# SD_Holder.net
KiCad netlist of a schematic drawn in Altium Designer
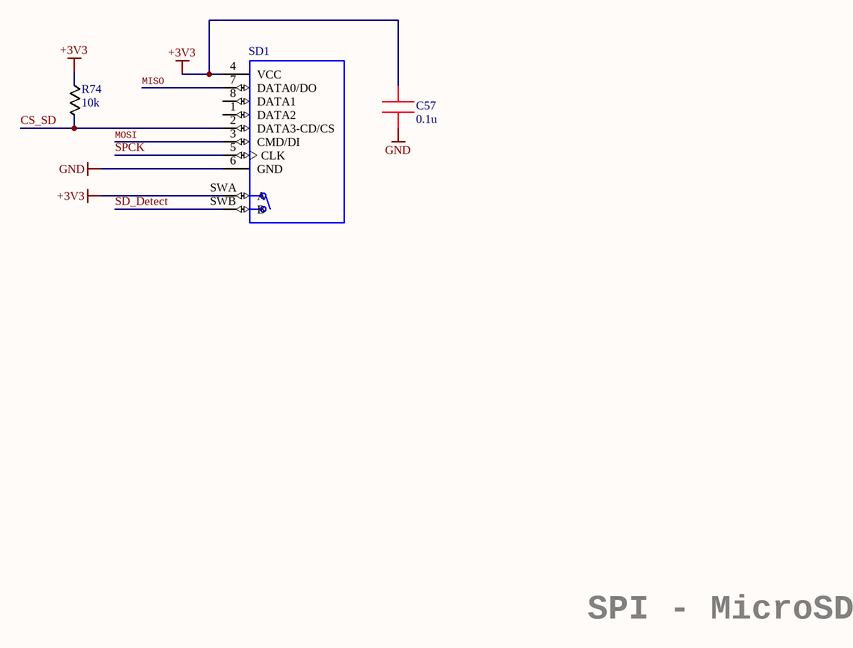
[diagram p0: SD Holder.SchDoc]

(export (version "E")
  (design (tool "Eeschema 10.0.6"))
  (components
    (comp (ref "C57")
      (value "0.1u")
      (footprint "0603")
      (fields (field (name "PART NUMBER") "GRM188R72A104KA35D"))
      (libsource (lib "kontr") (part "0603 CAP"))
    )
    (comp (ref "R74")
      (value "10k")
      (footprint "0603")
      (fields (field (name "PART NUMBER") "RC0603JR-0710K"))
      (libsource (lib "kontr") (part "0603 RES"))
    )
    (comp (ref "SD1")
      (value "~")
      (footprint "DM3AT-SF-PEJM5")
      (fields (field (name "PART NUMBER") "DM3AT-SF-PEJM5"))
      (libsource (lib "kontr") (part "DM3AT-SF-PEJM5"))
    )
  )
  (nets
    (net (code "1") (name "+3V3") (class "Default")
      (node (ref "C57") (pin "2") (pinfunction "2_2") (pintype "passive"))
      (node (ref "R74") (pin "1") (pintype "passive"))
      (node (ref "SD1") (pin "4") (pinfunction "VCC_4") (pintype "power_in"))
      (node (ref "SD1") (pin "SWA") (pinfunction "A_SWA") (pintype "bidirectional"))
    )
    (net (code "2") (name "/CS_SD") (class "Default")
      (node (ref "R74") (pin "2") (pintype "passive"))
      (node (ref "SD1") (pin "2") (pinfunction "DATA3-CD/CS_2") (pintype "bidirectional"))
    )
    (net (code "3") (name "/MISO") (class "Default")
      (node (ref "SD1") (pin "7") (pinfunction "DATA0/DO_7") (pintype "bidirectional"))
    )
    (net (code "4") (name "/MOSI") (class "Default")
      (node (ref "SD1") (pin "3") (pinfunction "CMD/DI_3") (pintype "bidirectional"))
    )
    (net (code "5") (name "/SD_Detect") (class "Default")
      (node (ref "SD1") (pin "SWB") (pinfunction "B_SWB") (pintype "bidirectional"))
    )
    (net (code "6") (name "/SPCK") (class "Default")
      (node (ref "SD1") (pin "5") (pinfunction "CLK_5") (pintype "bidirectional"))
    )
    (net (code "7") (name "GND") (class "Default")
      (node (ref "C57") (pin "1") (pinfunction "1_1") (pintype "passive"))
      (node (ref "SD1") (pin "6") (pinfunction "GND_6") (pintype "power_in"))
    )
    (net (code "8") (name "unconnected-(SD1-DATA1-Pad8)") (class "Default")
      (node (ref "SD1") (pin "8") (pinfunction "DATA1_8") (pintype "bidirectional"))
    )
    (net (code "9") (name "unconnected-(SD1-DATA2-Pad1)") (class "Default")
      (node (ref "SD1") (pin "1") (pinfunction "DATA2_1") (pintype "bidirectional"))
    )
  )
)
